# AuxSensor_Breakout.net
KiCad netlist of a schematic drawn in EAGLE
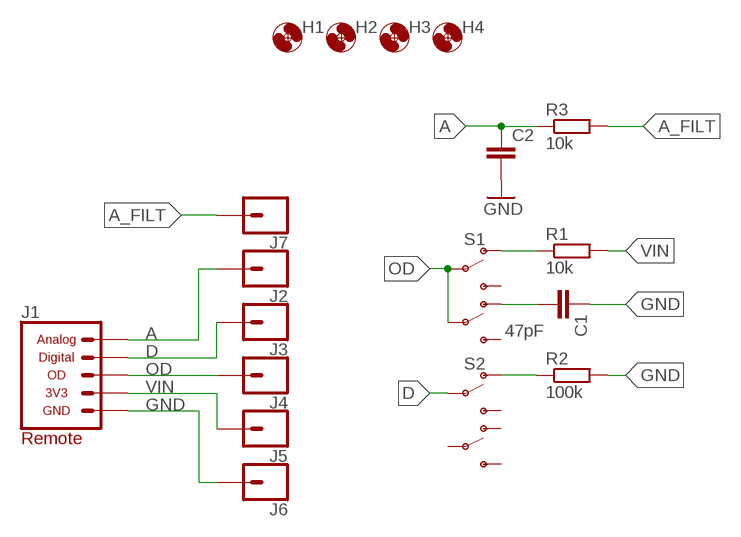
[diagram p0: schematic, sheet 1]

(export (version "E")
  (design (tool "Eeschema 10.0.6"))
  (components
    (comp (ref "C1")
      (value "47pF")
      (footprint "eagle-import:C0805")
      (libsource (lib "eagle-import") (part "C-EUC0805"))
    )
    (comp (ref "C2")
      (value "C-EU0.1UFC0805")
      (footprint "eagle-import:C0805")
      (fields (field (name "MF") "Kemet") (field (name "MPN") "C0805C104M3RACTU"))
      (libsource (lib "eagle-import") (part "C-EUC08050.1UF"))
    )
    (comp (ref "H1")
      (value "MOUNTING_HOLE4_NP")
      (footprint "eagle-import:4_40")
      (fields (field (name "MPN") "DNP"))
      (libsource (lib "eagle-import") (part "MOUNTING_HOLE4_NP"))
    )
    (comp (ref "H2")
      (value "MOUNTING_HOLE4_NP")
      (footprint "eagle-import:4_40")
      (fields (field (name "MPN") "DNP"))
      (libsource (lib "eagle-import") (part "MOUNTING_HOLE4_NP"))
    )
    (comp (ref "H3")
      (value "MOUNTING_HOLE4_NP")
      (footprint "eagle-import:4_40")
      (fields (field (name "MPN") "DNP"))
      (libsource (lib "eagle-import") (part "MOUNTING_HOLE4_NP"))
    )
    (comp (ref "H4")
      (value "MOUNTING_HOLE4_NP")
      (footprint "eagle-import:4_40")
      (fields (field (name "MPN") "DNP"))
      (libsource (lib "eagle-import") (part "MOUNTING_HOLE4_NP"))
    )
    (comp (ref "J1")
      (value "CONN_AUX_M12_REMOTE")
      (footprint "eagle-import:1X05_M12_TE_T41410")
      (fields (field (name "DISP") "Remote") (field (name "MF") "TE") (field (name "MPN") "T4141012051-000"))
      (libsource (lib "eagle-import") (part "CONN_AUX_M12_REMOTE"))
    )
    (comp (ref "J2")
      (value "CONN_BANANA_SOLDER")
      (footprint "eagle-import:CON_BANANA_575-4")
      (libsource (lib "eagle-import") (part "CONN_BANANA_SOLDER"))
    )
    (comp (ref "J3")
      (value "CONN_BANANA_SOLDER")
      (footprint "eagle-import:CON_BANANA_575-4")
      (libsource (lib "eagle-import") (part "CONN_BANANA_SOLDER"))
    )
    (comp (ref "J4")
      (value "CONN_BANANA_SOLDER")
      (footprint "eagle-import:CON_BANANA_575-4")
      (libsource (lib "eagle-import") (part "CONN_BANANA_SOLDER"))
    )
    (comp (ref "J5")
      (value "CONN_BANANA_SOLDER")
      (footprint "eagle-import:CON_BANANA_575-4")
      (libsource (lib "eagle-import") (part "CONN_BANANA_SOLDER"))
    )
    (comp (ref "J6")
      (value "CONN_BANANA_SOLDER")
      (footprint "eagle-import:CON_BANANA_575-4")
      (libsource (lib "eagle-import") (part "CONN_BANANA_SOLDER"))
    )
    (comp (ref "J7")
      (value "CONN_BANANA_SOLDER")
      (footprint "eagle-import:CON_BANANA_575-4")
      (libsource (lib "eagle-import") (part "CONN_BANANA_SOLDER"))
    )
    (comp (ref "R1")
      (value "10k")
      (footprint "eagle-import:R0805")
      (fields (field (name "MF") "Yageo") (field (name "MPN") "RC0805FR-0710KL"))
      (libsource (lib "eagle-import") (part "R-EU_R080510K"))
    )
    (comp (ref "R2")
      (value "100k")
      (footprint "eagle-import:R0805")
      (fields (field (name "MF") "Yageo") (field (name "MPN") "RC0805FR-07100KL"))
      (libsource (lib "eagle-import") (part "R-EU_R0805100K"))
    )
    (comp (ref "R3")
      (value "10k")
      (footprint "eagle-import:R0805")
      (fields (field (name "MF") "Yageo") (field (name "MPN") "RC0805FR-0710KL"))
      (libsource (lib "eagle-import") (part "R-EU_R080510K"))
    )
    (comp (ref "S1")
      (value "SWITCH_DPDTJS_GULLWING")
      (footprint "eagle-import:JS202011SCQN")
      (fields (field (name "MF") "C&K") (field (name "MPN") "JS202011SCQN"))
      (libsource (lib "eagle-import") (part "SWITCH_DPDTJS_GULLWING"))
    )
    (comp (ref "S2")
      (value "SWITCH_DPDTJS_GULLWING")
      (footprint "eagle-import:JS202011SCQN")
      (fields (field (name "MF") "C&K") (field (name "MPN") "JS202011SCQN"))
      (libsource (lib "eagle-import") (part "SWITCH_DPDTJS_GULLWING"))
    )
  )
  (nets
    (net (code "1") (name "A") (class "Default")
      (node (ref "C2") (pin "1") (pinfunction "1_1") (pintype "passive"))
      (node (ref "J1") (pin "4") (pinfunction "ANALOG_4") (pintype "passive"))
      (node (ref "J2") (pin "P$1") (pinfunction "1_P$1") (pintype "passive"))
      (node (ref "R3") (pin "1") (pinfunction "1_1") (pintype "passive"))
    )
    (net (code "2") (name "A_FILT") (class "Default")
      (node (ref "J7") (pin "P$1") (pinfunction "1_P$1") (pintype "passive"))
      (node (ref "R3") (pin "2") (pinfunction "2_2") (pintype "passive"))
    )
    (net (code "3") (name "D") (class "Default")
      (node (ref "J1") (pin "5") (pinfunction "DIGITAL_5") (pintype "passive"))
      (node (ref "J3") (pin "P$1") (pinfunction "1_P$1") (pintype "passive"))
      (node (ref "S2") (pin "2") (pinfunction "P1_2") (pintype "passive"))
    )
    (net (code "4") (name "GND") (class "Default")
      (node (ref "C1") (pin "1") (pinfunction "1_1") (pintype "passive"))
      (node (ref "C2") (pin "2") (pinfunction "2_2") (pintype "passive"))
      (node (ref "J1") (pin "3") (pinfunction "GND_3") (pintype "passive"))
      (node (ref "J6") (pin "P$1") (pinfunction "1_P$1") (pintype "passive"))
      (node (ref "R2") (pin "2") (pinfunction "2_2") (pintype "passive"))
    )
    (net (code "5") (name "Net-(S1-O1)") (class "Default")
      (node (ref "R1") (pin "1") (pinfunction "1_1") (pintype "passive"))
      (node (ref "S1") (pin "1") (pinfunction "O1_1") (pintype "passive"))
    )
    (net (code "6") (name "Net-(S1-O2)") (class "Default")
      (node (ref "C1") (pin "2") (pinfunction "2_2") (pintype "passive"))
      (node (ref "S1") (pin "6") (pinfunction "O2_6") (pintype "passive"))
    )
    (net (code "7") (name "Net-(S2-O1)") (class "Default")
      (node (ref "R2") (pin "1") (pinfunction "1_1") (pintype "passive"))
      (node (ref "S2") (pin "1") (pinfunction "O1_1") (pintype "passive"))
    )
    (net (code "8") (name "OD") (class "Default")
      (node (ref "J1") (pin "2") (pinfunction "DIGITAL_OPENDRAIN_2") (pintype "passive"))
      (node (ref "J4") (pin "P$1") (pinfunction "1_P$1") (pintype "passive"))
      (node (ref "S1") (pin "2") (pinfunction "P1_2") (pintype "passive"))
      (node (ref "S1") (pin "5") (pinfunction "P2_5") (pintype "passive"))
    )
    (net (code "9") (name "VIN") (class "Default")
      (node (ref "J1") (pin "1") (pinfunction "3V3_1") (pintype "passive"))
      (node (ref "J5") (pin "P$1") (pinfunction "1_P$1") (pintype "passive"))
      (node (ref "R1") (pin "2") (pinfunction "2_2") (pintype "passive"))
    )
    (net (code "10") (name "unconnected-(S1-S1-Pad3)") (class "Default")
      (node (ref "S1") (pin "3") (pinfunction "S1_3") (pintype "passive"))
    )
    (net (code "11") (name "unconnected-(S1-S2-Pad4)") (class "Default")
      (node (ref "S1") (pin "4") (pinfunction "S2_4") (pintype "passive"))
    )
    (net (code "12") (name "unconnected-(S2-O2-Pad6)") (class "Default")
      (node (ref "S2") (pin "6") (pinfunction "O2_6") (pintype "passive"))
    )
    (net (code "13") (name "unconnected-(S2-P2-Pad5)") (class "Default")
      (node (ref "S2") (pin "5") (pinfunction "P2_5") (pintype "passive"))
    )
    (net (code "14") (name "unconnected-(S2-S1-Pad3)") (class "Default")
      (node (ref "S2") (pin "3") (pinfunction "S1_3") (pintype "passive"))
    )
    (net (code "15") (name "unconnected-(S2-S2-Pad4)") (class "Default")
      (node (ref "S2") (pin "4") (pinfunction "S2_4") (pintype "passive"))
    )
  )
)
